# board_io_v2.net
KiCad netlist of a schematic drawn in EAGLE
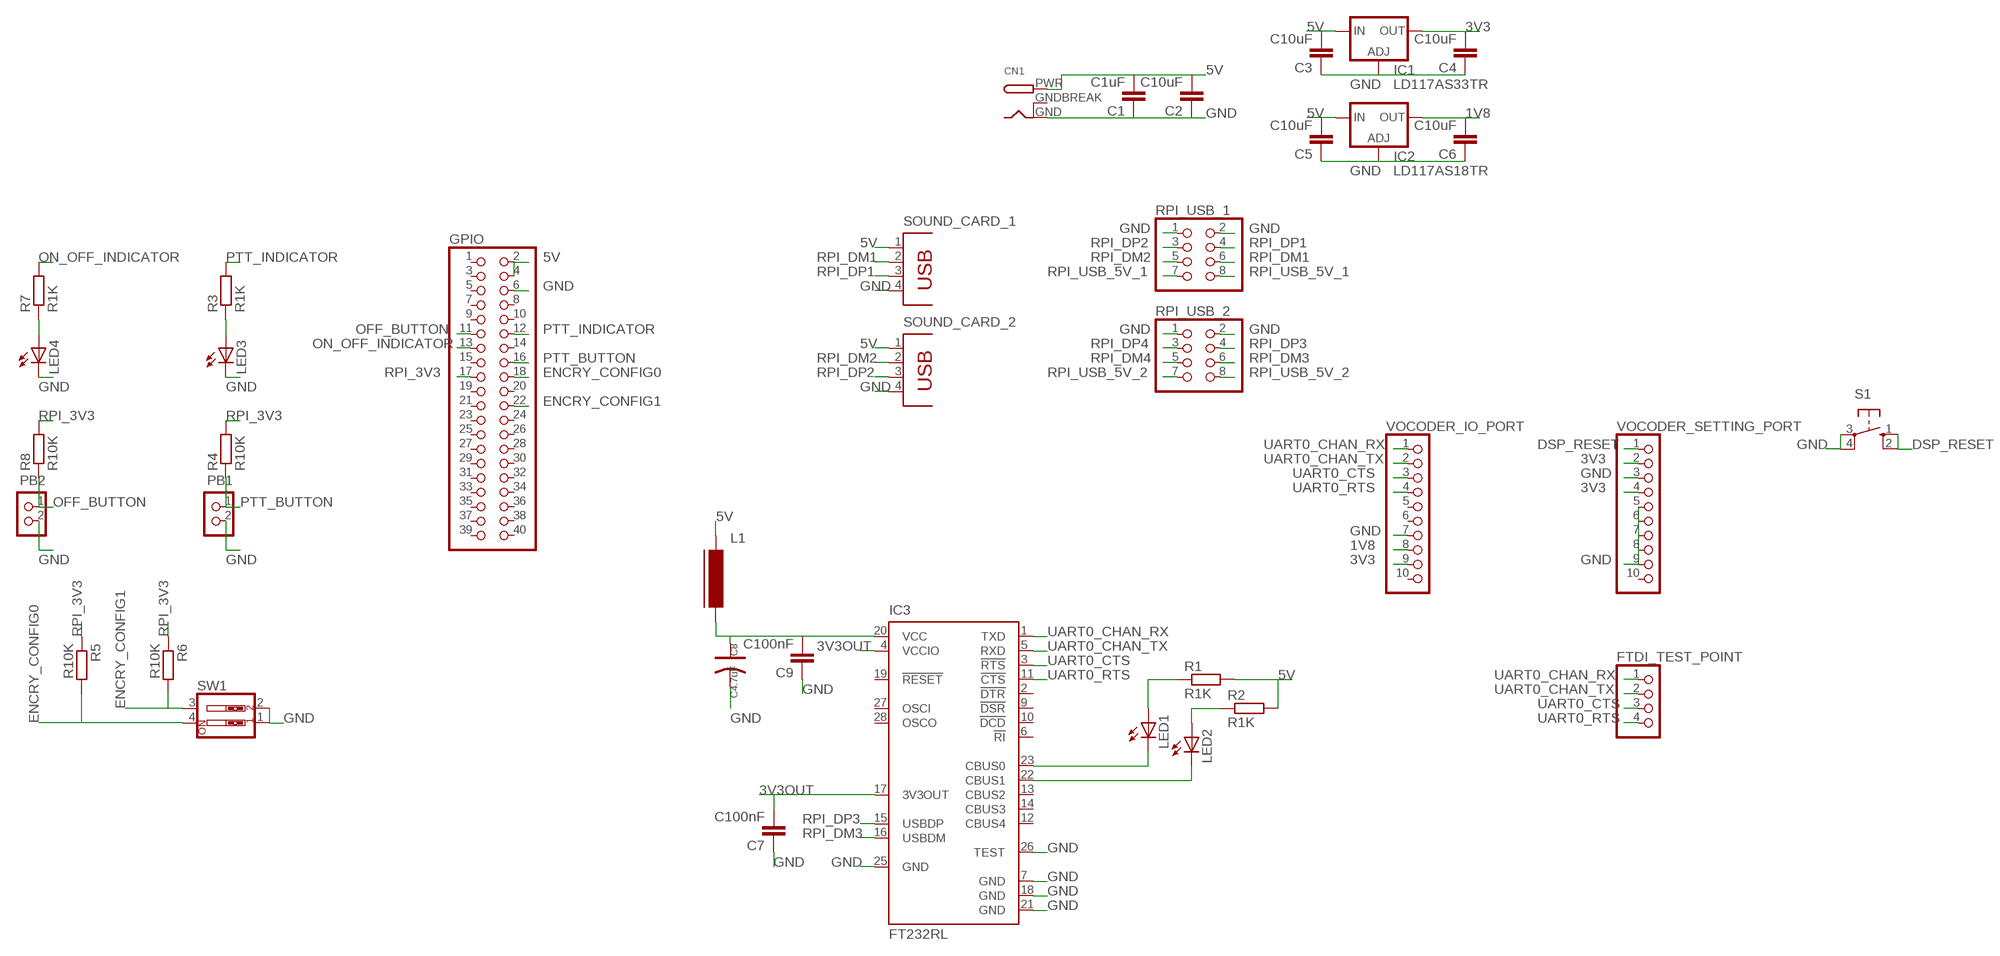
[diagram p0: schematic, sheet 1]

(export (version "E")
  (design (tool "Eeschema 10.0.6"))
  (components
    (comp (ref "C1")
      (value "C1uF")
      (footprint "eagle-import:C0805")
      (libsource (lib "eagle-import") (part "C-EUC0805"))
    )
    (comp (ref "C2")
      (value "C10uF")
      (footprint "eagle-import:C0805")
      (libsource (lib "eagle-import") (part "C-EUC0805"))
    )
    (comp (ref "C3")
      (value "C10uF")
      (footprint "eagle-import:C0805")
      (libsource (lib "eagle-import") (part "C-EUC0805"))
    )
    (comp (ref "C4")
      (value "C10uF")
      (footprint "eagle-import:C0805")
      (libsource (lib "eagle-import") (part "C-EUC0805"))
    )
    (comp (ref "C5")
      (value "C10uF")
      (footprint "eagle-import:C0805")
      (libsource (lib "eagle-import") (part "C-EUC0805"))
    )
    (comp (ref "C6")
      (value "C10uF")
      (footprint "eagle-import:C0805")
      (libsource (lib "eagle-import") (part "C-EUC0805"))
    )
    (comp (ref "C7")
      (value "C100nF")
      (footprint "eagle-import:C0805")
      (libsource (lib "eagle-import") (part "C-EUC0805"))
    )
    (comp (ref "C8")
      (value "C4.7uF")
      (footprint "eagle-import:AVX-C")
      (libsource (lib "eagle-import") (part "C-POLAR-C"))
    )
    (comp (ref "C9")
      (value "C100nF")
      (footprint "eagle-import:C0805")
      (libsource (lib "eagle-import") (part "C-EUC0805"))
    )
    (comp (ref "CN1")
      (value "DCBARRELPTH")
      (footprint "eagle-import:DCJACK_2MM_PTH")
      (libsource (lib "eagle-import") (part "DCBARRELPTH"))
    )
    (comp (ref "FTDI_TEST_POINT")
      (value "PINHD-1X4")
      (footprint "eagle-import:1X04")
      (libsource (lib "eagle-import") (part "PINHD-1X4"))
    )
    (comp (ref "GPIO")
      (value "PINHD-2X20")
      (footprint "eagle-import:2X20")
      (libsource (lib "eagle-import") (part "PINHD-2X20"))
    )
    (comp (ref "IC1")
      (value "LD117AS33TR")
      (footprint "eagle-import:SOT223")
      (libsource (lib "eagle-import") (part "LD117A?S33TR"))
    )
    (comp (ref "IC2")
      (value "LD117AS18TR")
      (footprint "eagle-import:SOT223")
      (libsource (lib "eagle-import") (part "LD117A?S18TR"))
    )
    (comp (ref "IC3")
      (value "FT232RL")
      (footprint "eagle-import:SSOP28")
      (libsource (lib "eagle-import") (part "FT232RL"))
    )
    (comp (ref "L1")
      (value "FERRITE-0603")
      (footprint "eagle-import:FB603")
      (libsource (lib "eagle-import") (part "FERRITE-0603"))
    )
    (comp (ref "LED1")
      (value "LEDCHIP-LED0805")
      (footprint "eagle-import:CHIP-LED0805")
      (libsource (lib "eagle-import") (part "LEDCHIP-LED0805"))
    )
    (comp (ref "LED2")
      (value "LEDCHIP-LED0805")
      (footprint "eagle-import:CHIP-LED0805")
      (libsource (lib "eagle-import") (part "LEDCHIP-LED0805"))
    )
    (comp (ref "LED3")
      (value "LEDCHIP-LED0805")
      (footprint "eagle-import:CHIP-LED0805")
      (libsource (lib "eagle-import") (part "LEDCHIP-LED0805"))
    )
    (comp (ref "LED4")
      (value "LEDCHIP-LED0805")
      (footprint "eagle-import:CHIP-LED0805")
      (libsource (lib "eagle-import") (part "LEDCHIP-LED0805"))
    )
    (comp (ref "PB1")
      (value "CON_HEADER_1X02-PTH")
      (footprint "eagle-import:M1X2")
      (libsource (lib "eagle-import") (part "CON_HEADER_1X02-PTH"))
    )
    (comp (ref "PB2")
      (value "CON_HEADER_1X02-PTH")
      (footprint "eagle-import:M1X2")
      (libsource (lib "eagle-import") (part "CON_HEADER_1X02-PTH"))
    )
    (comp (ref "R1")
      (value "R1K")
      (footprint "eagle-import:R0805")
      (libsource (lib "eagle-import") (part "R-EU_R0805"))
    )
    (comp (ref "R2")
      (value "R1K")
      (footprint "eagle-import:R0805")
      (libsource (lib "eagle-import") (part "R-EU_R0805"))
    )
    (comp (ref "R3")
      (value "R1K")
      (footprint "eagle-import:R0805")
      (libsource (lib "eagle-import") (part "R-EU_R0805"))
    )
    (comp (ref "R4")
      (value "R10K")
      (footprint "eagle-import:R0805")
      (libsource (lib "eagle-import") (part "R-EU_R0805"))
    )
    (comp (ref "R5")
      (value "R10K")
      (footprint "eagle-import:R0805")
      (libsource (lib "eagle-import") (part "R-EU_R0805"))
    )
    (comp (ref "R6")
      (value "R10K")
      (footprint "eagle-import:R0805")
      (libsource (lib "eagle-import") (part "R-EU_R0805"))
    )
    (comp (ref "R7")
      (value "R1K")
      (footprint "eagle-import:R0805")
      (libsource (lib "eagle-import") (part "R-EU_R0805"))
    )
    (comp (ref "R8")
      (value "R10K")
      (footprint "eagle-import:R0805")
      (libsource (lib "eagle-import") (part "R-EU_R0805"))
    )
    (comp (ref "RPI_USB_1")
      (value "PINHD-2X4")
      (footprint "eagle-import:2X04")
      (libsource (lib "eagle-import") (part "PINHD-2X4"))
    )
    (comp (ref "RPI_USB_2")
      (value "PINHD-2X4")
      (footprint "eagle-import:2X04")
      (libsource (lib "eagle-import") (part "PINHD-2X4"))
    )
    (comp (ref "S1")
      (value "10-XX")
      (footprint "eagle-import:B3F-10XX")
      (fields (field (name "MPN") "B3F-1000"))
      (libsource (lib "eagle-import") (part "10-XX"))
    )
    (comp (ref "SOUND_CARD_1")
      (value "PN87520")
      (footprint "eagle-import:PN87520")
      (libsource (lib "eagle-import") (part "PN87520"))
    )
    (comp (ref "SOUND_CARD_2")
      (value "PN87520")
      (footprint "eagle-import:PN87520")
      (fields (field (name "OC_FARNELL") "unknown") (field (name "OC_NEWARK") "unknown"))
      (libsource (lib "eagle-import") (part "PN87520"))
    )
    (comp (ref "SW1")
      (value "SW_DIP-2")
      (footprint "eagle-import:DIPSWITCH-02")
      (libsource (lib "eagle-import") (part "SW_DIP-2"))
    )
    (comp (ref "VOCODER_IO_PORT")
      (value "PINHD-1X10")
      (footprint "eagle-import:1X10")
      (libsource (lib "eagle-import") (part "PINHD-1X10"))
    )
    (comp (ref "VOCODER_SETTING_PORT")
      (value "PINHD-1X10")
      (footprint "eagle-import:1X10")
      (libsource (lib "eagle-import") (part "PINHD-1X10"))
    )
  )
  (nets
    (net (code "1") (name "/1V8") (class "Default")
      (node (ref "C6") (pin "2") (pinfunction "2_2") (pintype "passive"))
      (node (ref "IC2") (pin "4") (pinfunction "OUT_4") (pintype "passive"))
      (node (ref "VOCODER_IO_PORT") (pin "8") (pinfunction "8_8") (pintype "passive"))
    )
    (net (code "2") (name "/3V3") (class "Default")
      (node (ref "C4") (pin "2") (pinfunction "2_2") (pintype "passive"))
      (node (ref "IC1") (pin "4") (pinfunction "OUT_4") (pintype "passive"))
      (node (ref "VOCODER_IO_PORT") (pin "9") (pinfunction "9_9") (pintype "passive"))
      (node (ref "VOCODER_SETTING_PORT") (pin "2") (pinfunction "2_2") (pintype "passive"))
      (node (ref "VOCODER_SETTING_PORT") (pin "4") (pinfunction "4_4") (pintype "passive"))
    )
    (net (code "3") (name "/3V3OUT") (class "Default")
      (node (ref "C7") (pin "2") (pinfunction "2_2") (pintype "passive"))
      (node (ref "IC3") (pin "17") (pinfunction "3V3OUT_17") (pintype "output"))
      (node (ref "IC3") (pin "4") (pinfunction "VCCIO_4") (pintype "power_in"))
    )
    (net (code "4") (name "/5V") (class "Default")
      (node (ref "C1") (pin "2") (pinfunction "2_2") (pintype "passive"))
      (node (ref "C2") (pin "2") (pinfunction "2_2") (pintype "passive"))
      (node (ref "C3") (pin "2") (pinfunction "2_2") (pintype "passive"))
      (node (ref "C5") (pin "2") (pinfunction "2_2") (pintype "passive"))
      (node (ref "CN1") (pin "PWR") (pinfunction "PWR_PWR") (pintype "power_in"))
      (node (ref "GPIO") (pin "2") (pinfunction "2_2") (pintype "passive"))
      (node (ref "GPIO") (pin "4") (pinfunction "4_4") (pintype "passive"))
      (node (ref "IC1") (pin "3") (pinfunction "IN_3") (pintype "input"))
      (node (ref "IC2") (pin "3") (pinfunction "IN_3") (pintype "input"))
      (node (ref "L1") (pin "1") (pinfunction "1_1") (pintype "passive"))
      (node (ref "R1") (pin "2") (pinfunction "2_2") (pintype "passive"))
      (node (ref "R2") (pin "2") (pinfunction "2_2") (pintype "passive"))
      (node (ref "SOUND_CARD_1") (pin "1") (pinfunction "1_1") (pintype "passive"))
      (node (ref "SOUND_CARD_2") (pin "1") (pinfunction "1_1") (pintype "passive"))
    )
    (net (code "5") (name "/DSP_RESET") (class "Default")
      (node (ref "S1") (pin "1") (pinfunction "S_1") (pintype "passive"))
      (node (ref "S1") (pin "2") (pinfunction "S1_2") (pintype "passive"))
      (node (ref "VOCODER_SETTING_PORT") (pin "1") (pinfunction "1_1") (pintype "passive"))
    )
    (net (code "6") (name "/ENCRY_CONFIG0") (class "Default")
      (node (ref "GPIO") (pin "18") (pinfunction "18_18") (pintype "passive"))
      (node (ref "R5") (pin "2") (pinfunction "2_2") (pintype "passive"))
      (node (ref "SW1") (pin "4") (pinfunction "4_4") (pintype "passive"))
    )
    (net (code "7") (name "/ENCRY_CONFIG1") (class "Default")
      (node (ref "GPIO") (pin "22") (pinfunction "22_22") (pintype "passive"))
      (node (ref "R6") (pin "2") (pinfunction "2_2") (pintype "passive"))
      (node (ref "SW1") (pin "3") (pinfunction "3_3") (pintype "passive"))
    )
    (net (code "8") (name "/GND") (class "Default")
      (node (ref "C1") (pin "1") (pinfunction "1_1") (pintype "passive"))
      (node (ref "C2") (pin "1") (pinfunction "1_1") (pintype "passive"))
      (node (ref "C3") (pin "1") (pinfunction "1_1") (pintype "passive"))
      (node (ref "C4") (pin "1") (pinfunction "1_1") (pintype "passive"))
      (node (ref "C5") (pin "1") (pinfunction "1_1") (pintype "passive"))
      (node (ref "C6") (pin "1") (pinfunction "1_1") (pintype "passive"))
      (node (ref "C7") (pin "1") (pinfunction "1_1") (pintype "passive"))
      (node (ref "C8") (pin "-") (pinfunction "2_-") (pintype "bidirectional"))
      (node (ref "C9") (pin "1") (pinfunction "1_1") (pintype "passive"))
      (node (ref "CN1") (pin "GND") (pinfunction "GND_GND") (pintype "power_in"))
      (node (ref "GPIO") (pin "6") (pinfunction "6_6") (pintype "passive"))
      (node (ref "IC1") (pin "1") (pinfunction "ADJ_1") (pintype "input"))
      (node (ref "IC2") (pin "1") (pinfunction "ADJ_1") (pintype "input"))
      (node (ref "IC3") (pin "18") (pinfunction "GND_18") (pintype "power_in"))
      (node (ref "IC3") (pin "21") (pinfunction "GND_21") (pintype "power_in"))
      (node (ref "IC3") (pin "25") (pinfunction "GND_25") (pintype "power_in"))
      (node (ref "IC3") (pin "26") (pinfunction "TEST_26") (pintype "input"))
      (node (ref "IC3") (pin "7") (pinfunction "GND_7") (pintype "power_in"))
      (node (ref "LED3") (pin "C") (pinfunction "C_C") (pintype "passive"))
      (node (ref "LED4") (pin "C") (pinfunction "C_C") (pintype "passive"))
      (node (ref "PB1") (pin "2") (pinfunction "2_2") (pintype "passive"))
      (node (ref "PB2") (pin "2") (pinfunction "2_2") (pintype "passive"))
      (node (ref "RPI_USB_1") (pin "1") (pinfunction "1_1") (pintype "passive"))
      (node (ref "RPI_USB_1") (pin "2") (pinfunction "2_2") (pintype "passive"))
      (node (ref "RPI_USB_2") (pin "1") (pinfunction "1_1") (pintype "passive"))
      (node (ref "RPI_USB_2") (pin "2") (pinfunction "2_2") (pintype "passive"))
      (node (ref "S1") (pin "3") (pinfunction "P_3") (pintype "passive"))
      (node (ref "S1") (pin "4") (pinfunction "P1_4") (pintype "passive"))
      (node (ref "SOUND_CARD_1") (pin "4") (pinfunction "4_4") (pintype "passive"))
      (node (ref "SOUND_CARD_2") (pin "4") (pinfunction "4_4") (pintype "passive"))
      (node (ref "SW1") (pin "1") (pinfunction "1_1") (pintype "passive"))
      (node (ref "SW1") (pin "2") (pinfunction "2_2") (pintype "passive"))
      (node (ref "VOCODER_IO_PORT") (pin "7") (pinfunction "7_7") (pintype "passive"))
      (node (ref "VOCODER_SETTING_PORT") (pin "3") (pinfunction "3_3") (pintype "passive"))
      (node (ref "VOCODER_SETTING_PORT") (pin "5") (pinfunction "5_5") (pintype "passive"))
      (node (ref "VOCODER_SETTING_PORT") (pin "6") (pinfunction "6_6") (pintype "passive"))
      (node (ref "VOCODER_SETTING_PORT") (pin "7") (pinfunction "7_7") (pintype "passive"))
      (node (ref "VOCODER_SETTING_PORT") (pin "8") (pinfunction "8_8") (pintype "passive"))
      (node (ref "VOCODER_SETTING_PORT") (pin "9") (pinfunction "9_9") (pintype "passive"))
    )
    (net (code "9") (name "/GNDBREAK") (class "Default")
      (node (ref "CN1") (pin "GNDBREAK") (pinfunction "GNDBREAK_GNDBREAK") (pintype "power_in"))
    )
    (net (code "10") (name "/OFF_BUTTON") (class "Default")
      (node (ref "GPIO") (pin "11") (pinfunction "11_11") (pintype "passive"))
      (node (ref "PB2") (pin "1") (pinfunction "1_1") (pintype "passive"))
      (node (ref "R8") (pin "1") (pinfunction "1_1") (pintype "passive"))
    )
    (net (code "11") (name "/ON_OFF_INDICATOR") (class "Default")
      (node (ref "GPIO") (pin "13") (pinfunction "13_13") (pintype "passive"))
      (node (ref "R7") (pin "2") (pinfunction "2_2") (pintype "passive"))
    )
    (net (code "12") (name "/PTT_BUTTON") (class "Default")
      (node (ref "GPIO") (pin "16") (pinfunction "16_16") (pintype "passive"))
      (node (ref "PB1") (pin "1") (pinfunction "1_1") (pintype "passive"))
      (node (ref "R4") (pin "1") (pinfunction "1_1") (pintype "passive"))
    )
    (net (code "13") (name "/PTT_INDICATOR") (class "Default")
      (node (ref "GPIO") (pin "12") (pinfunction "12_12") (pintype "passive"))
      (node (ref "R3") (pin "2") (pinfunction "2_2") (pintype "passive"))
    )
    (net (code "14") (name "/RPI_3V3") (class "Default")
      (node (ref "GPIO") (pin "17") (pinfunction "17_17") (pintype "passive"))
      (node (ref "R4") (pin "2") (pinfunction "2_2") (pintype "passive"))
      (node (ref "R5") (pin "1") (pinfunction "1_1") (pintype "passive"))
      (node (ref "R6") (pin "1") (pinfunction "1_1") (pintype "passive"))
      (node (ref "R8") (pin "2") (pinfunction "2_2") (pintype "passive"))
    )
    (net (code "15") (name "/RPI_DM1") (class "Default")
      (node (ref "RPI_USB_1") (pin "6") (pinfunction "6_6") (pintype "passive"))
      (node (ref "SOUND_CARD_1") (pin "2") (pinfunction "2_2") (pintype "passive"))
    )
    (net (code "16") (name "/RPI_DM2") (class "Default")
      (node (ref "RPI_USB_1") (pin "5") (pinfunction "5_5") (pintype "passive"))
      (node (ref "SOUND_CARD_2") (pin "2") (pinfunction "2_2") (pintype "passive"))
    )
    (net (code "17") (name "/RPI_DM3") (class "Default")
      (node (ref "IC3") (pin "16") (pinfunction "USBDM_16") (pintype "bidirectional"))
      (node (ref "RPI_USB_2") (pin "6") (pinfunction "6_6") (pintype "passive"))
    )
    (net (code "18") (name "/RPI_DM4") (class "Default")
      (node (ref "RPI_USB_2") (pin "5") (pinfunction "5_5") (pintype "passive"))
    )
    (net (code "19") (name "/RPI_DP1") (class "Default")
      (node (ref "RPI_USB_1") (pin "4") (pinfunction "4_4") (pintype "passive"))
      (node (ref "SOUND_CARD_1") (pin "3") (pinfunction "3_3") (pintype "passive"))
    )
    (net (code "20") (name "/RPI_DP2") (class "Default")
      (node (ref "RPI_USB_1") (pin "3") (pinfunction "3_3") (pintype "passive"))
      (node (ref "SOUND_CARD_2") (pin "3") (pinfunction "3_3") (pintype "passive"))
    )
    (net (code "21") (name "/RPI_DP3") (class "Default")
      (node (ref "IC3") (pin "15") (pinfunction "USBDP_15") (pintype "bidirectional"))
      (node (ref "RPI_USB_2") (pin "4") (pinfunction "4_4") (pintype "passive"))
    )
    (net (code "22") (name "/RPI_DP4") (class "Default")
      (node (ref "RPI_USB_2") (pin "3") (pinfunction "3_3") (pintype "passive"))
    )
    (net (code "23") (name "/RPI_USB_5V_1") (class "Default")
      (node (ref "RPI_USB_1") (pin "7") (pinfunction "7_7") (pintype "passive"))
      (node (ref "RPI_USB_1") (pin "8") (pinfunction "8_8") (pintype "passive"))
    )
    (net (code "24") (name "/RPI_USB_5V_2") (class "Default")
      (node (ref "RPI_USB_2") (pin "7") (pinfunction "7_7") (pintype "passive"))
      (node (ref "RPI_USB_2") (pin "8") (pinfunction "8_8") (pintype "passive"))
    )
    (net (code "25") (name "/UART0_CHAN_RX") (class "Default")
      (node (ref "FTDI_TEST_POINT") (pin "1") (pinfunction "1_1") (pintype "passive"))
      (node (ref "IC3") (pin "1") (pinfunction "TXD_1") (pintype "output"))
      (node (ref "VOCODER_IO_PORT") (pin "1") (pinfunction "1_1") (pintype "passive"))
    )
    (net (code "26") (name "/UART0_CHAN_TX") (class "Default")
      (node (ref "FTDI_TEST_POINT") (pin "2") (pinfunction "2_2") (pintype "passive"))
      (node (ref "IC3") (pin "5") (pinfunction "RXD_5") (pintype "input"))
      (node (ref "VOCODER_IO_PORT") (pin "2") (pinfunction "2_2") (pintype "passive"))
    )
    (net (code "27") (name "/UART0_CTS") (class "Default")
      (node (ref "FTDI_TEST_POINT") (pin "3") (pinfunction "3_3") (pintype "passive"))
      (node (ref "IC3") (pin "3") (pinfunction "~{RTS}_3") (pintype "output"))
      (node (ref "VOCODER_IO_PORT") (pin "3") (pinfunction "3_3") (pintype "passive"))
    )
    (net (code "28") (name "/UART0_RTS") (class "Default")
      (node (ref "FTDI_TEST_POINT") (pin "4") (pinfunction "4_4") (pintype "passive"))
      (node (ref "IC3") (pin "11") (pinfunction "~{CTS}_11") (pintype "input"))
      (node (ref "VOCODER_IO_PORT") (pin "4") (pinfunction "4_4") (pintype "passive"))
    )
    (net (code "29") (name "Net-(C8-1)") (class "Default")
      (node (ref "C8") (pin "+") (pinfunction "1_+") (pintype "bidirectional"))
      (node (ref "C9") (pin "2") (pinfunction "2_2") (pintype "passive"))
      (node (ref "IC3") (pin "20") (pinfunction "VCC_20") (pintype "power_in"))
      (node (ref "L1") (pin "2") (pinfunction "2_2") (pintype "passive"))
    )
    (net (code "30") (name "Net-(IC3-CBUS0)") (class "Default")
      (node (ref "IC3") (pin "23") (pinfunction "CBUS0_23") (pintype "bidirectional"))
      (node (ref "LED1") (pin "C") (pinfunction "C_C") (pintype "passive"))
    )
    (net (code "31") (name "Net-(IC3-CBUS1)") (class "Default")
      (node (ref "IC3") (pin "22") (pinfunction "CBUS1_22") (pintype "bidirectional"))
      (node (ref "LED2") (pin "C") (pinfunction "C_C") (pintype "passive"))
    )
    (net (code "32") (name "Net-(LED1-PadA)") (class "Default")
      (node (ref "LED1") (pin "A") (pinfunction "A_A") (pintype "passive"))
      (node (ref "R1") (pin "1") (pinfunction "1_1") (pintype "passive"))
    )
    (net (code "33") (name "Net-(LED2-PadA)") (class "Default")
      (node (ref "LED2") (pin "A") (pinfunction "A_A") (pintype "passive"))
      (node (ref "R2") (pin "1") (pinfunction "1_1") (pintype "passive"))
    )
    (net (code "34") (name "Net-(LED3-PadA)") (class "Default")
      (node (ref "LED3") (pin "A") (pinfunction "A_A") (pintype "passive"))
      (node (ref "R3") (pin "1") (pinfunction "1_1") (pintype "passive"))
    )
    (net (code "35") (name "Net-(LED4-PadA)") (class "Default")
      (node (ref "LED4") (pin "A") (pinfunction "A_A") (pintype "passive"))
      (node (ref "R7") (pin "1") (pinfunction "1_1") (pintype "passive"))
    )
    (net (code "36") (name "unconnected-(GPIO-Pad1)") (class "Default")
      (node (ref "GPIO") (pin "1") (pinfunction "1_1") (pintype "passive"))
    )
    (net (code "37") (name "unconnected-(GPIO-Pad3)") (class "Default")
      (node (ref "GPIO") (pin "3") (pinfunction "3_3") (pintype "passive"))
    )
    (net (code "38") (name "unconnected-(GPIO-Pad5)") (class "Default")
      (node (ref "GPIO") (pin "5") (pinfunction "5_5") (pintype "passive"))
    )
    (net (code "39") (name "unconnected-(GPIO-Pad7)") (class "Default")
      (node (ref "GPIO") (pin "7") (pinfunction "7_7") (pintype "passive"))
    )
    (net (code "40") (name "unconnected-(GPIO-Pad8)") (class "Default")
      (node (ref "GPIO") (pin "8") (pinfunction "8_8") (pintype "passive"))
    )
    (net (code "41") (name "unconnected-(GPIO-Pad9)") (class "Default")
      (node (ref "GPIO") (pin "9") (pinfunction "9_9") (pintype "passive"))
    )
    (net (code "42") (name "unconnected-(GPIO-Pad10)") (class "Default")
      (node (ref "GPIO") (pin "10") (pinfunction "10_10") (pintype "passive"))
    )
    (net (code "43") (name "unconnected-(GPIO-Pad14)") (class "Default")
      (node (ref "GPIO") (pin "14") (pinfunction "14_14") (pintype "passive"))
    )
    (net (code "44") (name "unconnected-(GPIO-Pad15)") (class "Default")
      (node (ref "GPIO") (pin "15") (pinfunction "15_15") (pintype "passive"))
    )
    (net (code "45") (name "unconnected-(GPIO-Pad19)") (class "Default")
      (node (ref "GPIO") (pin "19") (pinfunction "19_19") (pintype "passive"))
    )
    (net (code "46") (name "unconnected-(GPIO-Pad20)") (class "Default")
      (node (ref "GPIO") (pin "20") (pinfunction "20_20") (pintype "passive"))
    )
    (net (code "47") (name "unconnected-(GPIO-Pad21)") (class "Default")
      (node (ref "GPIO") (pin "21") (pinfunction "21_21") (pintype "passive"))
    )
    (net (code "48") (name "unconnected-(GPIO-Pad23)") (class "Default")
      (node (ref "GPIO") (pin "23") (pinfunction "23_23") (pintype "passive"))
    )
    (net (code "49") (name "unconnected-(GPIO-Pad24)") (class "Default")
      (node (ref "GPIO") (pin "24") (pinfunction "24_24") (pintype "passive"))
    )
    (net (code "50") (name "unconnected-(GPIO-Pad25)") (class "Default")
      (node (ref "GPIO") (pin "25") (pinfunction "25_25") (pintype "passive"))
    )
    (net (code "51") (name "unconnected-(GPIO-Pad26)") (class "Default")
      (node (ref "GPIO") (pin "26") (pinfunction "26_26") (pintype "passive"))
    )
    (net (code "52") (name "unconnected-(GPIO-Pad27)") (class "Default")
      (node (ref "GPIO") (pin "27") (pinfunction "27_27") (pintype "passive"))
    )
    (net (code "53") (name "unconnected-(GPIO-Pad28)") (class "Default")
      (node (ref "GPIO") (pin "28") (pinfunction "28_28") (pintype "passive"))
    )
    (net (code "54") (name "unconnected-(GPIO-Pad29)") (class "Default")
      (node (ref "GPIO") (pin "29") (pinfunction "29_29") (pintype "passive"))
    )
    (net (code "55") (name "unconnected-(GPIO-Pad30)") (class "Default")
      (node (ref "GPIO") (pin "30") (pinfunction "30_30") (pintype "passive"))
    )
    (net (code "56") (name "unconnected-(GPIO-Pad31)") (class "Default")
      (node (ref "GPIO") (pin "31") (pinfunction "31_31") (pintype "passive"))
    )
    (net (code "57") (name "unconnected-(GPIO-Pad32)") (class "Default")
      (node (ref "GPIO") (pin "32") (pinfunction "32_32") (pintype "passive"))
    )
    (net (code "58") (name "unconnected-(GPIO-Pad33)") (class "Default")
      (node (ref "GPIO") (pin "33") (pinfunction "33_33") (pintype "passive"))
    )
    (net (code "59") (name "unconnected-(GPIO-Pad34)") (class "Default")
      (node (ref "GPIO") (pin "34") (pinfunction "34_34") (pintype "passive"))
    )
    (net (code "60") (name "unconnected-(GPIO-Pad35)") (class "Default")
      (node (ref "GPIO") (pin "35") (pinfunction "35_35") (pintype "passive"))
    )
    (net (code "61") (name "unconnected-(GPIO-Pad36)") (class "Default")
      (node (ref "GPIO") (pin "36") (pinfunction "36_36") (pintype "passive"))
    )
    (net (code "62") (name "unconnected-(GPIO-Pad37)") (class "Default")
      (node (ref "GPIO") (pin "37") (pinfunction "37_37") (pintype "passive"))
    )
    (net (code "63") (name "unconnected-(GPIO-Pad38)") (class "Default")
      (node (ref "GPIO") (pin "38") (pinfunction "38_38") (pintype "passive"))
    )
    (net (code "64") (name "unconnected-(GPIO-Pad39)") (class "Default")
      (node (ref "GPIO") (pin "39") (pinfunction "39_39") (pintype "passive"))
    )
    (net (code "65") (name "unconnected-(GPIO-Pad40)") (class "Default")
      (node (ref "GPIO") (pin "40") (pinfunction "40_40") (pintype "passive"))
    )
    (net (code "66") (name "unconnected-(IC3-CBUS2-Pad13)") (class "Default")
      (node (ref "IC3") (pin "13") (pinfunction "CBUS2_13") (pintype "bidirectional"))
    )
    (net (code "67") (name "unconnected-(IC3-CBUS3-Pad14)") (class "Default")
      (node (ref "IC3") (pin "14") (pinfunction "CBUS3_14") (pintype "bidirectional"))
    )
    (net (code "68") (name "unconnected-(IC3-CBUS4-Pad12)") (class "Default")
      (node (ref "IC3") (pin "12") (pinfunction "CBUS4_12") (pintype "bidirectional"))
    )
    (net (code "69") (name "unconnected-(IC3-OSCI-Pad27)") (class "Default")
      (node (ref "IC3") (pin "27") (pinfunction "OSCI_27") (pintype "input"))
    )
    (net (code "70") (name "unconnected-(IC3-OSCO-Pad28)") (class "Default")
      (node (ref "IC3") (pin "28") (pinfunction "OSCO_28") (pintype "output"))
    )
    (net (code "71") (name "unconnected-(IC3-~{DCD}-Pad10)") (class "Default")
      (node (ref "IC3") (pin "10") (pinfunction "~{DCD}_10") (pintype "input"))
    )
    (net (code "72") (name "unconnected-(IC3-~{DSR}-Pad9)") (class "Default")
      (node (ref "IC3") (pin "9") (pinfunction "~{DSR}_9") (pintype "input"))
    )
    (net (code "73") (name "unconnected-(IC3-~{DTR}-Pad2)") (class "Default")
      (node (ref "IC3") (pin "2") (pinfunction "~{DTR}_2") (pintype "output"))
    )
    (net (code "74") (name "unconnected-(IC3-~{RESET}-Pad19)") (class "Default")
      (node (ref "IC3") (pin "19") (pinfunction "~{RESET}_19") (pintype "input"))
    )
    (net (code "75") (name "unconnected-(IC3-~{RI}-Pad6)") (class "Default")
      (node (ref "IC3") (pin "6") (pinfunction "~{RI}_6") (pintype "input"))
    )
    (net (code "76") (name "unconnected-(VOCODER_IO_PORT-Pad5)") (class "Default")
      (node (ref "VOCODER_IO_PORT") (pin "5") (pinfunction "5_5") (pintype "passive"))
    )
    (net (code "77") (name "unconnected-(VOCODER_IO_PORT-Pad6)") (class "Default")
      (node (ref "VOCODER_IO_PORT") (pin "6") (pinfunction "6_6") (pintype "passive"))
    )
    (net (code "78") (name "unconnected-(VOCODER_IO_PORT-Pad10)") (class "Default")
      (node (ref "VOCODER_IO_PORT") (pin "10") (pinfunction "10_10") (pintype "passive"))
    )
    (net (code "79") (name "unconnected-(VOCODER_SETTING_PORT-Pad10)") (class "Default")
      (node (ref "VOCODER_SETTING_PORT") (pin "10") (pinfunction "10_10") (pintype "passive"))
    )
  )
)
